# Amplifier.net
KiCad netlist of a schematic drawn in Altium Designer
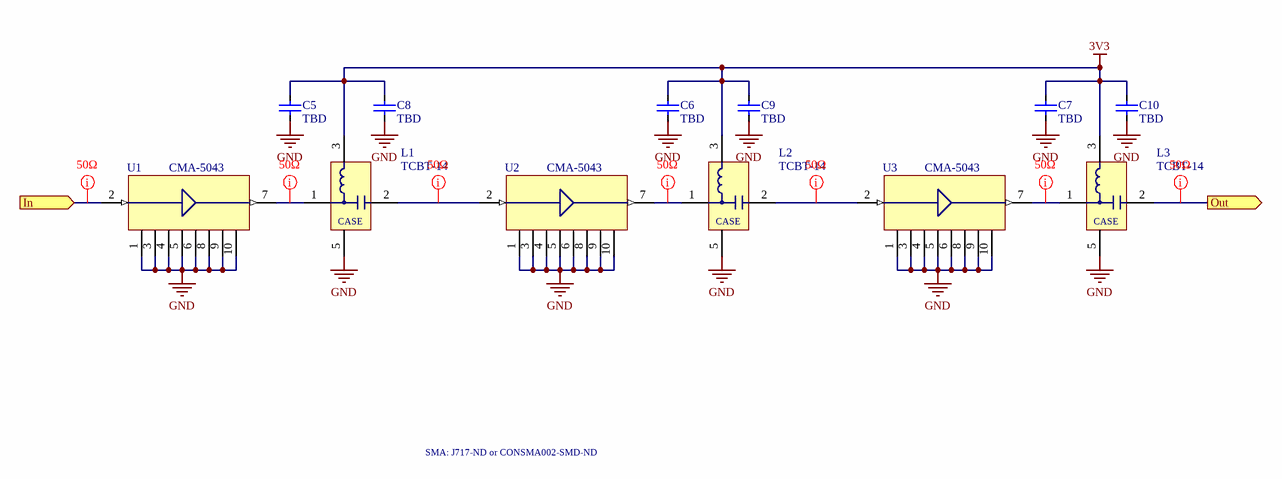
[diagram p0: Amplifier.SchDoc]

(export (version "E")
  (design (tool "Eeschema 10.0.6"))
  (components
    (comp (ref "C5")
      (value "TBD")
      (footprint "0805C")
      (description "Capacitor")
      (fields (field (name "Comment") "Cap") (field (name "PUBLISHER") "Altium Limited"))
      (libsource (lib "Miscellaneous Devices") (part "Cap"))
    )
    (comp (ref "C6")
      (value "TBD")
      (footprint "0805C")
      (description "Capacitor")
      (fields (field (name "Comment") "Cap") (field (name "PUBLISHER") "Altium Limited"))
      (libsource (lib "Miscellaneous Devices") (part "Cap"))
    )
    (comp (ref "C7")
      (value "TBD")
      (footprint "0805C")
      (description "Capacitor")
      (fields (field (name "Comment") "Cap") (field (name "PUBLISHER") "Altium Limited"))
      (libsource (lib "Miscellaneous Devices") (part "Cap"))
    )
    (comp (ref "C8")
      (value "TBD")
      (footprint "0805C")
      (description "Capacitor")
      (fields (field (name "Comment") "Cap") (field (name "PUBLISHER") "Altium Limited"))
      (libsource (lib "Miscellaneous Devices") (part "Cap"))
    )
    (comp (ref "C9")
      (value "TBD")
      (footprint "0805C")
      (description "Capacitor")
      (fields (field (name "Comment") "Cap") (field (name "PUBLISHER") "Altium Limited"))
      (libsource (lib "Miscellaneous Devices") (part "Cap"))
    )
    (comp (ref "C10")
      (value "TBD")
      (footprint "0805C")
      (description "Capacitor")
      (fields (field (name "Comment") "Cap") (field (name "PUBLISHER") "Altium Limited"))
      (libsource (lib "Miscellaneous Devices") (part "Cap"))
    )
    (comp (ref "L1")
      (value "TCBT-14")
      (footprint "GU1414")
      (description "Surface Mount 10 MHz to 10 GHz Bias Tee")
      (libsource (lib "RF Components") (part "TCBT-14"))
    )
    (comp (ref "L2")
      (value "TCBT-14")
      (footprint "GU1414")
      (description "Surface Mount 10 MHz to 10 GHz Bias Tee")
      (libsource (lib "RF Components") (part "TCBT-14"))
    )
    (comp (ref "L3")
      (value "TCBT-14")
      (footprint "GU1414")
      (description "Surface Mount 10 MHz to 10 GHz Bias Tee")
      (libsource (lib "RF Components") (part "TCBT-14"))
    )
    (comp (ref "U1")
      (value "CMA-5043")
      (footprint "DL1721")
      (description "Low Noise, High IP3 Monolithic Amplifier")
      (libsource (lib "RF Components") (part "CMA-5043"))
    )
    (comp (ref "U2")
      (value "CMA-5043")
      (footprint "DL1721")
      (description "Low Noise, High IP3 Monolithic Amplifier")
      (libsource (lib "RF Components") (part "CMA-5043"))
    )
    (comp (ref "U3")
      (value "CMA-5043")
      (footprint "DL1721")
      (description "Low Noise, High IP3 Monolithic Amplifier")
      (libsource (lib "RF Components") (part "CMA-5043"))
    )
  )
  (nets
    (net (code "1") (name "/In") (class "Default")
      (node (ref "U1") (pin "2") (pinfunction "In_2") (pintype "input"))
    )
    (net (code "2") (name "/Out") (class "Default")
      (node (ref "L3") (pin "2") (pinfunction "RF_2") (pintype "passive"))
    )
    (net (code "3") (name "3V3") (class "Default")
      (node (ref "C10") (pin "2") (pinfunction "2_2") (pintype "passive"))
      (node (ref "C5") (pin "2") (pinfunction "2_2") (pintype "passive"))
      (node (ref "C6") (pin "2") (pinfunction "2_2") (pintype "passive"))
      (node (ref "C7") (pin "2") (pinfunction "2_2") (pintype "passive"))
      (node (ref "C8") (pin "2") (pinfunction "2_2") (pintype "passive"))
      (node (ref "C9") (pin "2") (pinfunction "2_2") (pintype "passive"))
      (node (ref "L1") (pin "3") (pinfunction "DC_3") (pintype "passive"))
      (node (ref "L2") (pin "3") (pinfunction "DC_3") (pintype "passive"))
      (node (ref "L3") (pin "3") (pinfunction "DC_3") (pintype "passive"))
    )
    (net (code "4") (name "GND") (class "Default")
      (node (ref "C10") (pin "1") (pinfunction "1_1") (pintype "passive"))
      (node (ref "C5") (pin "1") (pinfunction "1_1") (pintype "passive"))
      (node (ref "C6") (pin "1") (pinfunction "1_1") (pintype "passive"))
      (node (ref "C7") (pin "1") (pinfunction "1_1") (pintype "passive"))
      (node (ref "C8") (pin "1") (pinfunction "1_1") (pintype "passive"))
      (node (ref "C9") (pin "1") (pinfunction "1_1") (pintype "passive"))
      (node (ref "L1") (pin "5") (pinfunction "CASE_5") (pintype "passive"))
      (node (ref "L2") (pin "5") (pinfunction "CASE_5") (pintype "passive"))
      (node (ref "L3") (pin "5") (pinfunction "CASE_5") (pintype "passive"))
      (node (ref "U1") (pin "1") (pinfunction "Gnd_1") (pintype "passive"))
      (node (ref "U1") (pin "10") (pinfunction "Gnd_10") (pintype "power_in"))
      (node (ref "U1") (pin "3") (pinfunction "Gnd_3") (pintype "power_in"))
      (node (ref "U1") (pin "4") (pinfunction "Gnd_4") (pintype "power_in"))
      (node (ref "U1") (pin "5") (pinfunction "Gnd_5") (pintype "power_in"))
      (node (ref "U1") (pin "6") (pinfunction "Gnd_6") (pintype "power_in"))
      (node (ref "U1") (pin "8") (pinfunction "Gnd_8") (pintype "power_in"))
      (node (ref "U1") (pin "9") (pinfunction "Gnd_9") (pintype "power_in"))
      (node (ref "U2") (pin "1") (pinfunction "Gnd_1") (pintype "passive"))
      (node (ref "U2") (pin "10") (pinfunction "Gnd_10") (pintype "power_in"))
      (node (ref "U2") (pin "3") (pinfunction "Gnd_3") (pintype "power_in"))
      (node (ref "U2") (pin "4") (pinfunction "Gnd_4") (pintype "power_in"))
      (node (ref "U2") (pin "5") (pinfunction "Gnd_5") (pintype "power_in"))
      (node (ref "U2") (pin "6") (pinfunction "Gnd_6") (pintype "power_in"))
      (node (ref "U2") (pin "8") (pinfunction "Gnd_8") (pintype "power_in"))
      (node (ref "U2") (pin "9") (pinfunction "Gnd_9") (pintype "power_in"))
      (node (ref "U3") (pin "1") (pinfunction "Gnd_1") (pintype "passive"))
      (node (ref "U3") (pin "10") (pinfunction "Gnd_10") (pintype "power_in"))
      (node (ref "U3") (pin "3") (pinfunction "Gnd_3") (pintype "power_in"))
      (node (ref "U3") (pin "4") (pinfunction "Gnd_4") (pintype "power_in"))
      (node (ref "U3") (pin "5") (pinfunction "Gnd_5") (pintype "power_in"))
      (node (ref "U3") (pin "6") (pinfunction "Gnd_6") (pintype "power_in"))
      (node (ref "U3") (pin "8") (pinfunction "Gnd_8") (pintype "power_in"))
      (node (ref "U3") (pin "9") (pinfunction "Gnd_9") (pintype "power_in"))
    )
    (net (code "5") (name "Net-(L1-RF)") (class "Default")
      (node (ref "L1") (pin "2") (pinfunction "RF_2") (pintype "passive"))
      (node (ref "U2") (pin "2") (pinfunction "In_2") (pintype "input"))
    )
    (net (code "6") (name "Net-(L1-RF+DC)") (class "Default")
      (node (ref "L1") (pin "1") (pinfunction "RF+DC_1") (pintype "passive"))
      (node (ref "U1") (pin "7") (pinfunction "Gnd_7") (pintype "output"))
    )
    (net (code "7") (name "Net-(L2-RF)") (class "Default")
      (node (ref "L2") (pin "2") (pinfunction "RF_2") (pintype "passive"))
      (node (ref "U3") (pin "2") (pinfunction "In_2") (pintype "input"))
    )
    (net (code "8") (name "Net-(L2-RF+DC)") (class "Default")
      (node (ref "L2") (pin "1") (pinfunction "RF+DC_1") (pintype "passive"))
      (node (ref "U2") (pin "7") (pinfunction "Gnd_7") (pintype "output"))
    )
    (net (code "9") (name "Net-(L3-RF+DC)") (class "Default")
      (node (ref "L3") (pin "1") (pinfunction "RF+DC_1") (pintype "passive"))
      (node (ref "U3") (pin "7") (pinfunction "Gnd_7") (pintype "output"))
    )
    (net (code "10") (name "unconnected-(L1-NC-Pad4)") (class "Default")
      (node (ref "L1") (pin "4") (pinfunction "NC_4") (pintype "passive"))
    )
    (net (code "11") (name "unconnected-(L2-NC-Pad4)") (class "Default")
      (node (ref "L2") (pin "4") (pinfunction "NC_4") (pintype "passive"))
    )
    (net (code "12") (name "unconnected-(L3-NC-Pad4)") (class "Default")
      (node (ref "L3") (pin "4") (pinfunction "NC_4") (pintype "passive"))
    )
  )
)
